# Wilssen_core_v0_204a.net
KiCad netlist of a schematic drawn in EAGLE
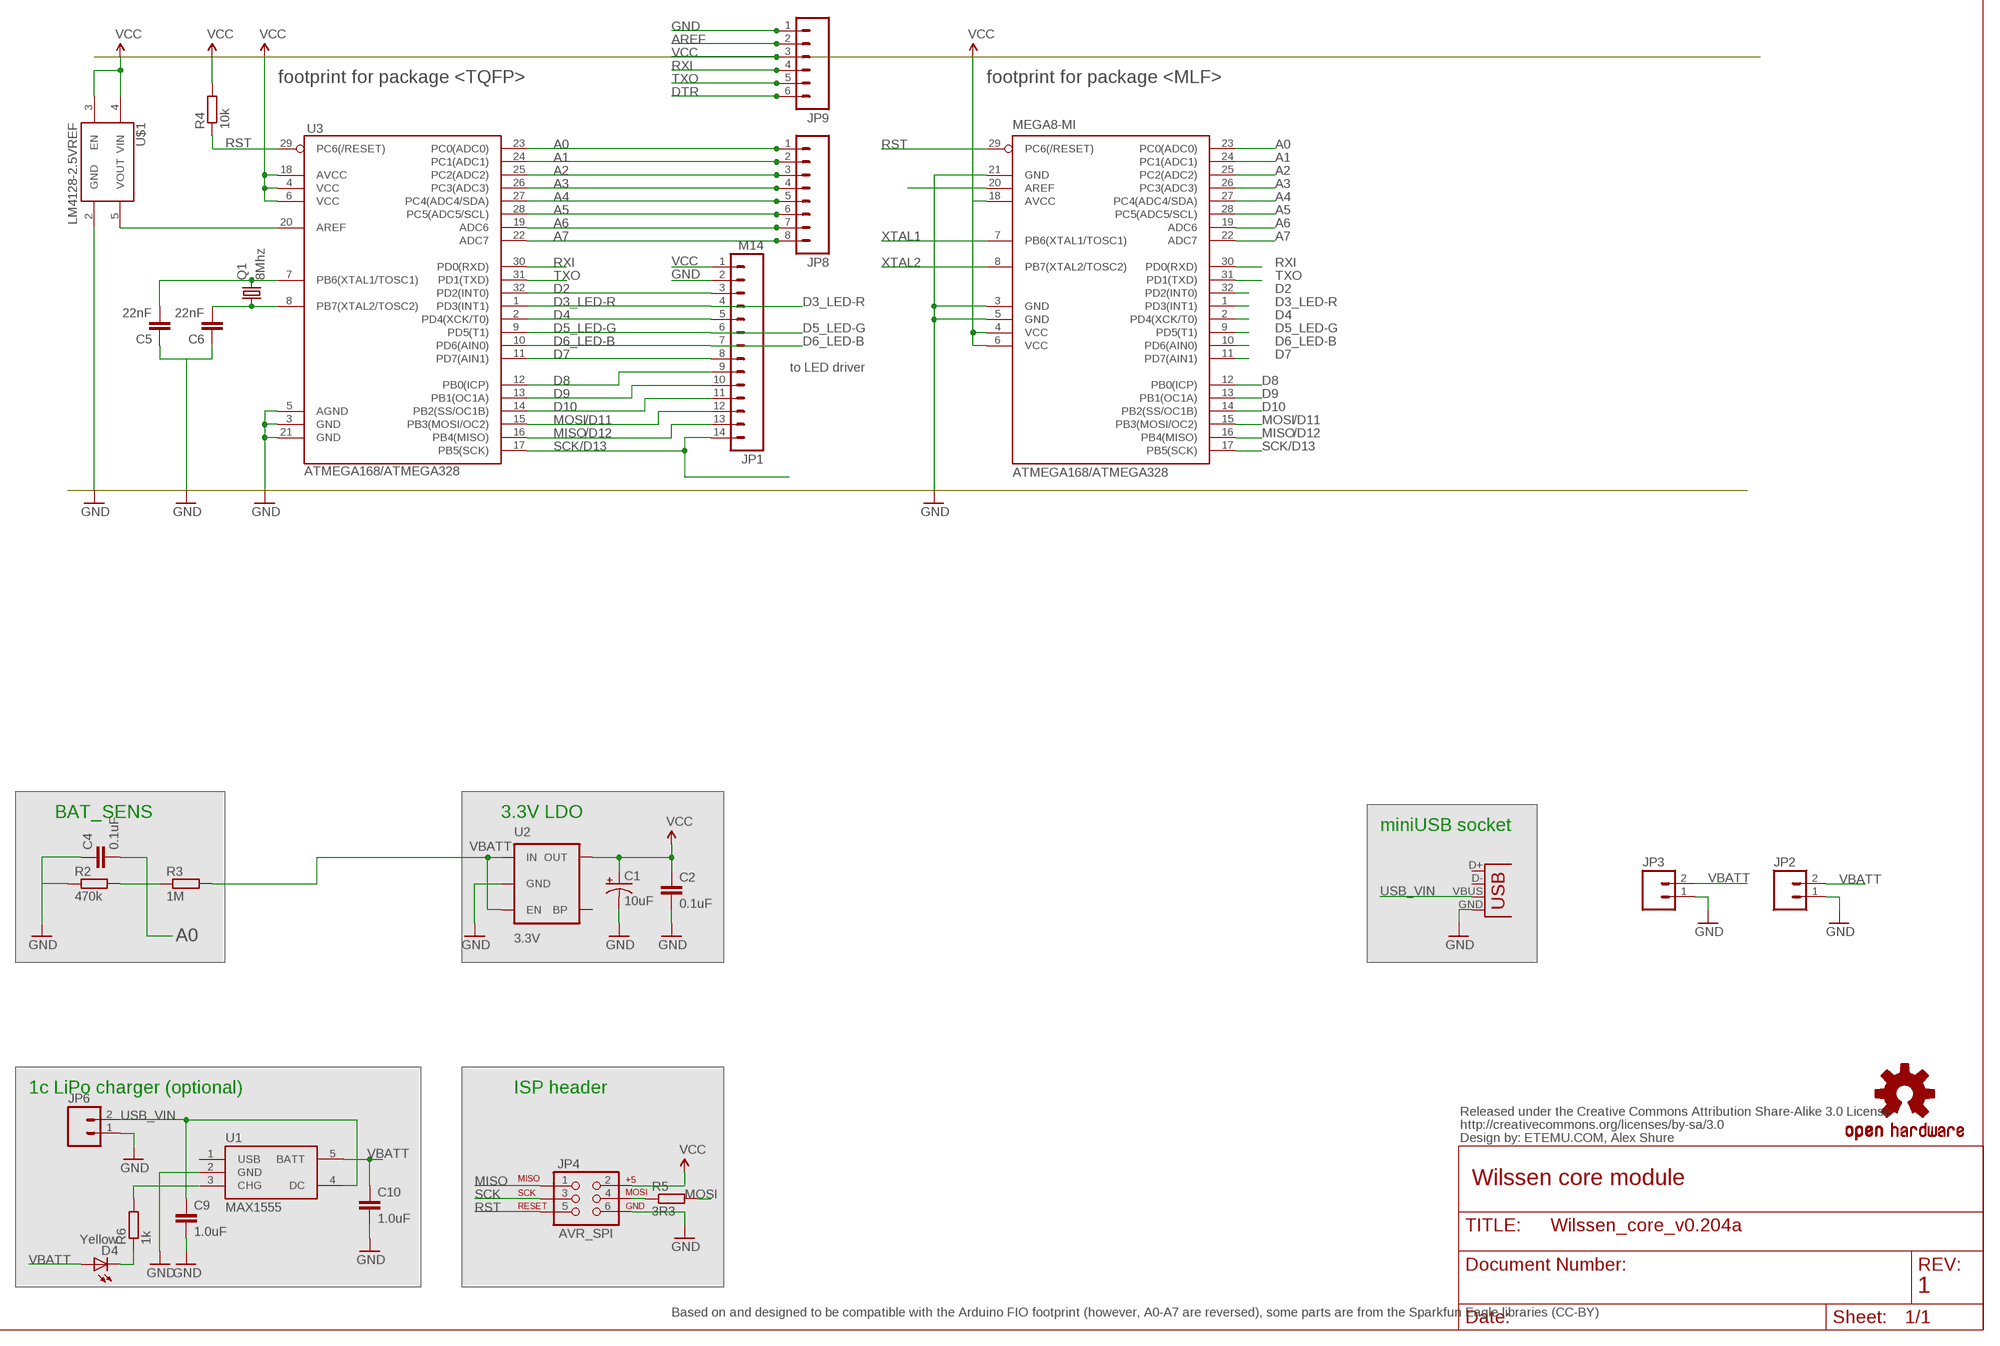
[diagram p0: schematic, sheet 1, part 1 of 2]
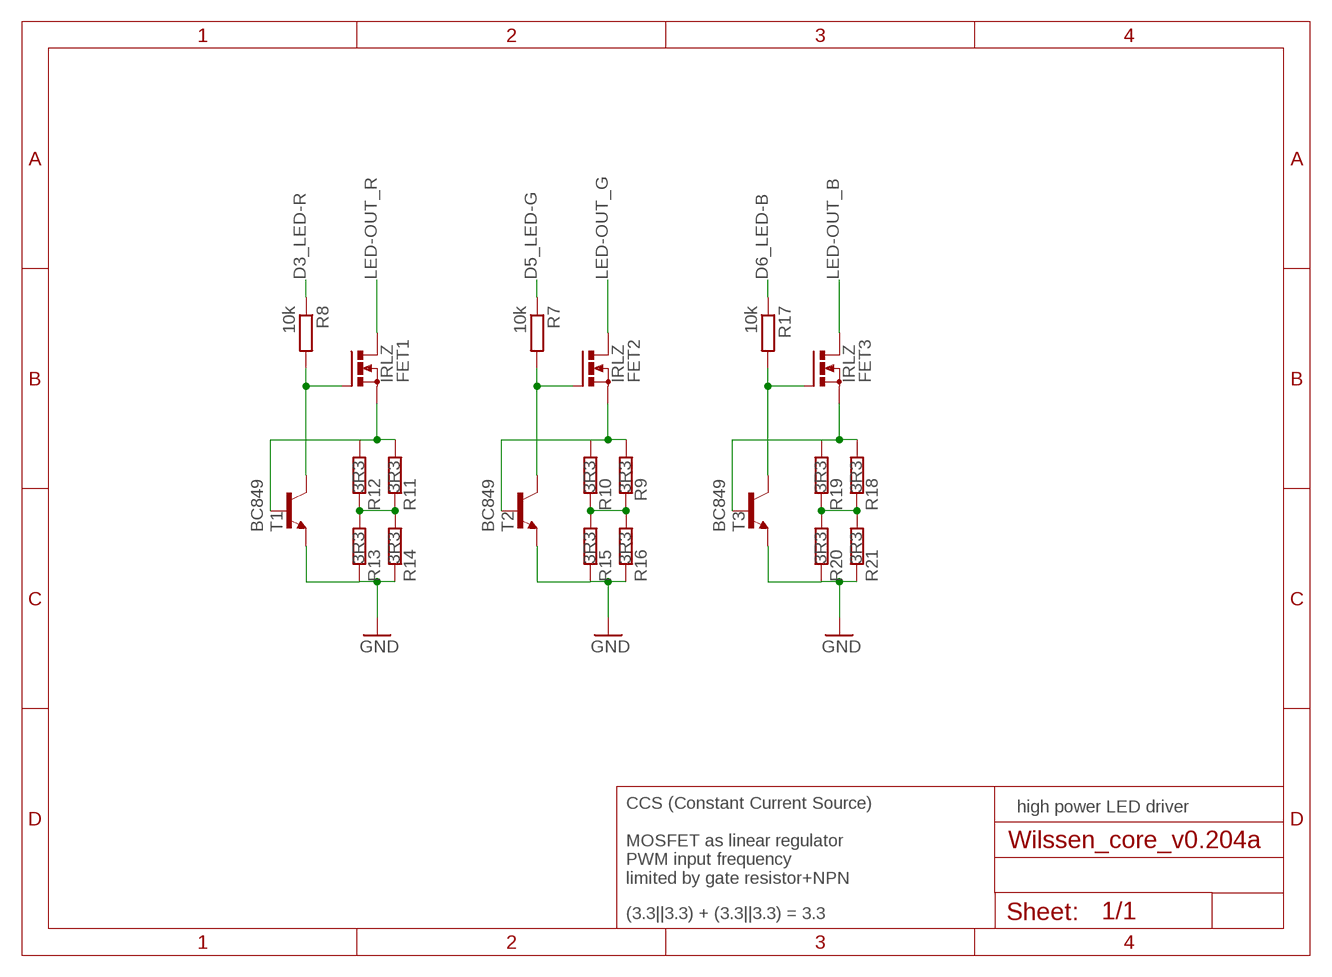
[diagram p1: schematic, sheet 1, part 2 of 2]

(export (version "E")
  (design (tool "Eeschema 10.0.6"))
  (components
    (comp (ref "ATMEGA168/ATMEGA328")
      (value "MEGA8-MI")
      (footprint "eagle-import:MLF32")
      (fields (field (name "MPN") "ATMEGA88PA-MU"))
      (libsource (lib "eagle-import") (part "MEGA8-MI"))
    )
    (comp (ref "C1")
      (value "10uF")
      (footprint "eagle-import:EIA3216")
      (libsource (lib "eagle-import") (part "CAP_POL1206"))
    )
    (comp (ref "C2")
      (value "0.1uF")
      (footprint "eagle-import:0805")
      (libsource (lib "eagle-import") (part "CAP0805"))
    )
    (comp (ref "C4")
      (value "0.1uF")
      (footprint "eagle-import:0805")
      (libsource (lib "eagle-import") (part "CAP0805"))
    )
    (comp (ref "C5")
      (value "22nF")
      (footprint "eagle-import:0805")
      (libsource (lib "eagle-import") (part "CAP0805"))
    )
    (comp (ref "C6")
      (value "22nF")
      (footprint "eagle-import:0805")
      (libsource (lib "eagle-import") (part "CAP0805"))
    )
    (comp (ref "C9")
      (value "1.0uF")
      (footprint "eagle-import:0805")
      (libsource (lib "eagle-import") (part "CAP0805"))
    )
    (comp (ref "C10")
      (value "1.0uF")
      (footprint "eagle-import:0805")
      (libsource (lib "eagle-import") (part "CAP0805"))
    )
    (comp (ref "CC_TEXT1")
      (value "CREATIVE_COMMONS")
      (footprint "eagle-import:CREATIVE_COMMONS")
      (libsource (lib "eagle-import") (part "CREATIVE_COMMONS"))
    )
    (comp (ref "D4")
      (value "Yellow")
      (footprint "eagle-import:LED-0603")
      (libsource (lib "eagle-import") (part "LED0603"))
    )
    (comp (ref "FET1")
      (value "IRLZ")
      (footprint "eagle-import:TO220BV")
      (libsource (lib "eagle-import") (part "PMOSFET_NTO220BV"))
    )
    (comp (ref "FET2")
      (value "IRLZ")
      (footprint "eagle-import:TO220BV")
      (libsource (lib "eagle-import") (part "PMOSFET_NTO220BV"))
    )
    (comp (ref "FET3")
      (value "IRLZ")
      (footprint "eagle-import:TO220BV")
      (libsource (lib "eagle-import") (part "PMOSFET_NTO220BV"))
    )
    (comp (ref "JP1")
      (value "M14")
      (footprint "eagle-import:1X14")
      (libsource (lib "eagle-import") (part "M14"))
    )
    (comp (ref "JP2")
      (value "M02PTH")
      (footprint "eagle-import:1X02")
      (libsource (lib "eagle-import") (part "M02PTH"))
    )
    (comp (ref "JP3")
      (value "M02-JST-2MM-SMT")
      (footprint "eagle-import:S2B-PH")
      (libsource (lib "eagle-import") (part "M02-JST-2MM-SMT"))
    )
    (comp (ref "JP4")
      (value "AVR_SPI")
      (footprint "eagle-import:2X3")
      (libsource (lib "eagle-import") (part "AVR_SPI_PRG_6PTH"))
    )
    (comp (ref "JP6")
      (value "M02PTH")
      (footprint "eagle-import:1X02")
      (libsource (lib "eagle-import") (part "M02PTH"))
    )
    (comp (ref "JP8")
      (value "M081X08")
      (footprint "eagle-import:1X08")
      (libsource (lib "eagle-import") (part "M081X08"))
    )
    (comp (ref "JP9")
      (value "M06SIP")
      (footprint "eagle-import:1X06")
      (libsource (lib "eagle-import") (part "M06SIP"))
    )
    (comp (ref "LOGO1")
      (value "OSHW-LOGOS")
      (footprint "eagle-import:OSHW-LOGO-S")
      (libsource (lib "eagle-import") (part "OSHW-LOGOS"))
    )
    (comp (ref "Q1")
      (value "8Mhz")
      (footprint "eagle-import:SM49")
      (libsource (lib "eagle-import") (part "CRYSTALSM49"))
    )
    (comp (ref "R2")
      (value "470k")
      (footprint "eagle-import:R0805")
      (libsource (lib "eagle-import") (part "R-EU_R0805"))
    )
    (comp (ref "R3")
      (value "1M")
      (footprint "eagle-import:R0805")
      (libsource (lib "eagle-import") (part "R-EU_R0805"))
    )
    (comp (ref "R4")
      (value "10k")
      (footprint "eagle-import:R0805")
      (libsource (lib "eagle-import") (part "R-EU_R0805"))
    )
    (comp (ref "R5")
      (value "3R3")
      (footprint "eagle-import:R1206")
      (libsource (lib "eagle-import") (part "R-EU_R1206"))
    )
    (comp (ref "R6")
      (value "1k")
      (footprint "eagle-import:R0805")
      (libsource (lib "eagle-import") (part "R-EU_R0805"))
    )
    (comp (ref "R7")
      (value "10k")
      (footprint "eagle-import:R0805")
      (libsource (lib "eagle-import") (part "resistor_R-EU_R0805"))
    )
    (comp (ref "R8")
      (value "10k")
      (footprint "eagle-import:R0805")
      (libsource (lib "eagle-import") (part "resistor_R-EU_R0805"))
    )
    (comp (ref "R9")
      (value "3R3")
      (footprint "eagle-import:R1206")
      (libsource (lib "eagle-import") (part "resistor_R-EU_R1206"))
    )
    (comp (ref "R10")
      (value "3R3")
      (footprint "eagle-import:R1206")
      (libsource (lib "eagle-import") (part "resistor_R-EU_R1206"))
    )
    (comp (ref "R11")
      (value "3R3")
      (footprint "eagle-import:R1206")
      (libsource (lib "eagle-import") (part "resistor_R-EU_R1206"))
    )
    (comp (ref "R12")
      (value "3R3")
      (footprint "eagle-import:R1206")
      (libsource (lib "eagle-import") (part "resistor_R-EU_R1206"))
    )
    (comp (ref "R13")
      (value "3R3")
      (footprint "eagle-import:R1206")
      (libsource (lib "eagle-import") (part "resistor_R-EU_R1206"))
    )
    (comp (ref "R14")
      (value "3R3")
      (footprint "eagle-import:R1206")
      (libsource (lib "eagle-import") (part "resistor_R-EU_R1206"))
    )
    (comp (ref "R15")
      (value "3R3")
      (footprint "eagle-import:R1206")
      (libsource (lib "eagle-import") (part "resistor_R-EU_R1206"))
    )
    (comp (ref "R16")
      (value "3R3")
      (footprint "eagle-import:R1206")
      (libsource (lib "eagle-import") (part "resistor_R-EU_R1206"))
    )
    (comp (ref "R17")
      (value "10k")
      (footprint "eagle-import:R0805")
      (libsource (lib "eagle-import") (part "resistor_R-EU_R0805"))
    )
    (comp (ref "R18")
      (value "3R3")
      (footprint "eagle-import:R1206")
      (libsource (lib "eagle-import") (part "resistor_R-EU_R1206"))
    )
    (comp (ref "R19")
      (value "3R3")
      (footprint "eagle-import:R1206")
      (libsource (lib "eagle-import") (part "resistor_R-EU_R1206"))
    )
    (comp (ref "R20")
      (value "3R3")
      (footprint "eagle-import:R1206")
      (libsource (lib "eagle-import") (part "resistor_R-EU_R1206"))
    )
    (comp (ref "R21")
      (value "3R3")
      (footprint "eagle-import:R1206")
      (libsource (lib "eagle-import") (part "resistor_R-EU_R1206"))
    )
    (comp (ref "T1")
      (value "BC849")
      (footprint "eagle-import:SOT23")
      (libsource (lib "eagle-import") (part "BC849"))
    )
    (comp (ref "T2")
      (value "BC849")
      (footprint "eagle-import:SOT23")
      (libsource (lib "eagle-import") (part "BC849"))
    )
    (comp (ref "T3")
      (value "BC849")
      (footprint "eagle-import:SOT23")
      (libsource (lib "eagle-import") (part "BC849"))
    )
    (comp (ref "U$1")
      (value "LM4128-2.5VREF")
      (footprint "eagle-import:SOT23-5")
      (libsource (lib "eagle-import") (part "LM4128-2.5VREF"))
    )
    (comp (ref "U1")
      (value "MAX1555")
      (footprint "eagle-import:SOT23-5")
      (libsource (lib "eagle-import") (part "MAX1555"))
    )
    (comp (ref "U2")
      (value "3.3V")
      (footprint "eagle-import:SOT23-5")
      (libsource (lib "eagle-import") (part "V_REG_LDOSMD"))
    )
    (comp (ref "U3")
      (value "ATMEGA168/ATMEGA328")
      (footprint "eagle-import:TQFP32-08")
      (libsource (lib "eagle-import") (part "ATMEGA168"))
    )
    (comp (ref "X1")
      (value "USBSMD")
      (footprint "eagle-import:USB-MINIB")
      (libsource (lib "eagle-import") (part "USBSMD"))
    )
  )
  (nets
    (net (code "1") (name "/A0") (class "Default")
      (node (ref "ATMEGA168/ATMEGA328") (pin "23") (pinfunction "PC0(ADC0)_23") (pintype "bidirectional"))
      (node (ref "C4") (pin "2") (pinfunction "2_2") (pintype "passive"))
      (node (ref "JP8") (pin "1") (pinfunction "1_1") (pintype "passive"))
      (node (ref "R2") (pin "2") (pinfunction "2_2") (pintype "passive"))
      (node (ref "R3") (pin "1") (pinfunction "1_1") (pintype "passive"))
      (node (ref "U3") (pin "23") (pinfunction "PC0(ADC0)_23") (pintype "bidirectional"))
    )
    (net (code "2") (name "/A1") (class "Default")
      (node (ref "ATMEGA168/ATMEGA328") (pin "24") (pinfunction "PC1(ADC1)_24") (pintype "bidirectional"))
      (node (ref "JP8") (pin "2") (pinfunction "2_2") (pintype "passive"))
      (node (ref "U3") (pin "24") (pinfunction "PC1(ADC1)_24") (pintype "bidirectional"))
    )
    (net (code "3") (name "/A2") (class "Default")
      (node (ref "ATMEGA168/ATMEGA328") (pin "25") (pinfunction "PC2(ADC2)_25") (pintype "bidirectional"))
      (node (ref "JP8") (pin "3") (pinfunction "3_3") (pintype "passive"))
      (node (ref "U3") (pin "25") (pinfunction "PC2(ADC2)_25") (pintype "bidirectional"))
    )
    (net (code "4") (name "/A3") (class "Default")
      (node (ref "ATMEGA168/ATMEGA328") (pin "26") (pinfunction "PC3(ADC3)_26") (pintype "bidirectional"))
      (node (ref "JP8") (pin "4") (pinfunction "4_4") (pintype "passive"))
      (node (ref "U3") (pin "26") (pinfunction "PC3(ADC3)_26") (pintype "bidirectional"))
    )
    (net (code "5") (name "/A4") (class "Default")
      (node (ref "ATMEGA168/ATMEGA328") (pin "27") (pinfunction "PC4(ADC4/SDA)_27") (pintype "bidirectional"))
      (node (ref "JP8") (pin "5") (pinfunction "5_5") (pintype "passive"))
      (node (ref "U3") (pin "27") (pinfunction "PC4(ADC4/SDA)_27") (pintype "bidirectional"))
    )
    (net (code "6") (name "/A5") (class "Default")
      (node (ref "ATMEGA168/ATMEGA328") (pin "28") (pinfunction "PC5(ADC5/SCL)_28") (pintype "bidirectional"))
      (node (ref "JP8") (pin "6") (pinfunction "6_6") (pintype "passive"))
      (node (ref "U3") (pin "28") (pinfunction "PC5(ADC5/SCL)_28") (pintype "bidirectional"))
    )
    (net (code "7") (name "/A6") (class "Default")
      (node (ref "ATMEGA168/ATMEGA328") (pin "19") (pinfunction "ADC6_19") (pintype "bidirectional"))
      (node (ref "JP8") (pin "7") (pinfunction "7_7") (pintype "passive"))
      (node (ref "U3") (pin "19") (pinfunction "ADC6_19") (pintype "bidirectional"))
    )
    (net (code "8") (name "/A7") (class "Default")
      (node (ref "ATMEGA168/ATMEGA328") (pin "22") (pinfunction "ADC7_22") (pintype "bidirectional"))
      (node (ref "JP8") (pin "8") (pinfunction "8_8") (pintype "passive"))
      (node (ref "U3") (pin "22") (pinfunction "ADC7_22") (pintype "bidirectional"))
    )
    (net (code "9") (name "/AREF") (class "Default")
      (node (ref "ATMEGA168/ATMEGA328") (pin "20") (pinfunction "AREF_20") (pintype "passive"))
      (node (ref "JP9") (pin "2") (pinfunction "2_2") (pintype "passive"))
      (node (ref "U$1") (pin "5") (pinfunction "VOUT_5") (pintype "bidirectional"))
      (node (ref "U3") (pin "20") (pinfunction "AREF_20") (pintype "bidirectional"))
    )
    (net (code "10") (name "/D2") (class "Default")
      (node (ref "ATMEGA168/ATMEGA328") (pin "32") (pinfunction "PD2(INT0)_32") (pintype "bidirectional"))
      (node (ref "JP1") (pin "3") (pinfunction "3_3") (pintype "passive"))
      (node (ref "U3") (pin "32") (pinfunction "PD2(INT0)_32") (pintype "bidirectional"))
    )
    (net (code "11") (name "/D3_LED-R") (class "Default")
      (node (ref "ATMEGA168/ATMEGA328") (pin "1") (pinfunction "PD3(INT1)_1") (pintype "bidirectional"))
      (node (ref "JP1") (pin "4") (pinfunction "4_4") (pintype "passive"))
      (node (ref "R8") (pin "1") (pinfunction "1_1") (pintype "passive"))
      (node (ref "U3") (pin "1") (pinfunction "PD3(INT1)_1") (pintype "bidirectional"))
    )
    (net (code "12") (name "/D4") (class "Default")
      (node (ref "ATMEGA168/ATMEGA328") (pin "2") (pinfunction "PD4(XCK/T0)_2") (pintype "bidirectional"))
      (node (ref "JP1") (pin "5") (pinfunction "5_5") (pintype "passive"))
      (node (ref "U3") (pin "2") (pinfunction "PD4(XCK/T0)_2") (pintype "bidirectional"))
    )
    (net (code "13") (name "/D5_LED-G") (class "Default")
      (node (ref "ATMEGA168/ATMEGA328") (pin "9") (pinfunction "PD5(T1)_9") (pintype "bidirectional"))
      (node (ref "JP1") (pin "6") (pinfunction "6_6") (pintype "passive"))
      (node (ref "R7") (pin "1") (pinfunction "1_1") (pintype "passive"))
      (node (ref "U3") (pin "9") (pinfunction "PD5(T1)_9") (pintype "bidirectional"))
    )
    (net (code "14") (name "/D6_LED-B") (class "Default")
      (node (ref "ATMEGA168/ATMEGA328") (pin "10") (pinfunction "PD6(AIN0)_10") (pintype "bidirectional"))
      (node (ref "JP1") (pin "7") (pinfunction "7_7") (pintype "passive"))
      (node (ref "R17") (pin "1") (pinfunction "1_1") (pintype "passive"))
      (node (ref "U3") (pin "10") (pinfunction "PD6(AIN0)_10") (pintype "bidirectional"))
    )
    (net (code "15") (name "/D7") (class "Default")
      (node (ref "ATMEGA168/ATMEGA328") (pin "11") (pinfunction "PD7(AIN1)_11") (pintype "bidirectional"))
      (node (ref "JP1") (pin "8") (pinfunction "8_8") (pintype "passive"))
      (node (ref "U3") (pin "11") (pinfunction "PD7(AIN1)_11") (pintype "bidirectional"))
    )
    (net (code "16") (name "/D8") (class "Default")
      (node (ref "ATMEGA168/ATMEGA328") (pin "12") (pinfunction "PB0(ICP)_12") (pintype "bidirectional"))
      (node (ref "JP1") (pin "9") (pinfunction "9_9") (pintype "passive"))
      (node (ref "U3") (pin "12") (pinfunction "PB0(ICP)_12") (pintype "bidirectional"))
    )
    (net (code "17") (name "/D9") (class "Default")
      (node (ref "ATMEGA168/ATMEGA328") (pin "13") (pinfunction "PB1(OC1A)_13") (pintype "bidirectional"))
      (node (ref "JP1") (pin "10") (pinfunction "10_10") (pintype "passive"))
      (node (ref "U3") (pin "13") (pinfunction "PB1(OC1A)_13") (pintype "bidirectional"))
    )
    (net (code "18") (name "/D10") (class "Default")
      (node (ref "ATMEGA168/ATMEGA328") (pin "14") (pinfunction "PB2(SS/OC1B)_14") (pintype "bidirectional"))
      (node (ref "JP1") (pin "11") (pinfunction "11_11") (pintype "passive"))
      (node (ref "U3") (pin "14") (pinfunction "PB2(SS/OC1B)_14") (pintype "bidirectional"))
    )
    (net (code "19") (name "/DTR") (class "Default")
      (node (ref "JP9") (pin "6") (pinfunction "6_6") (pintype "passive"))
    )
    (net (code "20") (name "/LED-OUT_B") (class "Default")
      (node (ref "FET3") (pin "D") (pinfunction "D_D") (pintype "passive"))
    )
    (net (code "21") (name "/LED-OUT_G") (class "Default")
      (node (ref "FET2") (pin "D") (pinfunction "D_D") (pintype "passive"))
    )
    (net (code "22") (name "/LED-OUT_R") (class "Default")
      (node (ref "FET1") (pin "D") (pinfunction "D_D") (pintype "passive"))
    )
    (net (code "23") (name "/MISO") (class "Default")
      (node (ref "ATMEGA168/ATMEGA328") (pin "16") (pinfunction "PB4(MISO)_16") (pintype "bidirectional"))
      (node (ref "JP1") (pin "13") (pinfunction "13_13") (pintype "passive"))
      (node (ref "JP4") (pin "1") (pinfunction "1_1") (pintype "passive"))
      (node (ref "U3") (pin "16") (pinfunction "PB4(MISO)_16") (pintype "bidirectional"))
    )
    (net (code "24") (name "/MOSI") (class "Default")
      (node (ref "ATMEGA168/ATMEGA328") (pin "15") (pinfunction "PB3(MOSI/OC2)_15") (pintype "bidirectional"))
      (node (ref "JP1") (pin "12") (pinfunction "12_12") (pintype "passive"))
      (node (ref "R5") (pin "2") (pinfunction "2_2") (pintype "passive"))
      (node (ref "U3") (pin "15") (pinfunction "PB3(MOSI/OC2)_15") (pintype "bidirectional"))
    )
    (net (code "25") (name "/RST") (class "Default")
      (node (ref "ATMEGA168/ATMEGA328") (pin "29") (pinfunction "PC6(/RESET)_29") (pintype "bidirectional"))
      (node (ref "JP4") (pin "5") (pinfunction "5_5") (pintype "passive"))
      (node (ref "R4") (pin "1") (pinfunction "1_1") (pintype "passive"))
      (node (ref "U3") (pin "29") (pinfunction "PC6(/RESET)_29") (pintype "bidirectional"))
    )
    (net (code "26") (name "/RXI") (class "Default")
      (node (ref "ATMEGA168/ATMEGA328") (pin "30") (pinfunction "PD0(RXD)_30") (pintype "bidirectional"))
      (node (ref "JP9") (pin "4") (pinfunction "4_4") (pintype "passive"))
      (node (ref "U3") (pin "30") (pinfunction "PD0(RXD)_30") (pintype "bidirectional"))
    )
    (net (code "27") (name "/SCK") (class "Default")
      (node (ref "ATMEGA168/ATMEGA328") (pin "17") (pinfunction "PB5(SCK)_17") (pintype "bidirectional"))
      (node (ref "JP1") (pin "14") (pinfunction "14_14") (pintype "passive"))
      (node (ref "JP4") (pin "3") (pinfunction "3_3") (pintype "passive"))
      (node (ref "U3") (pin "17") (pinfunction "PB5(SCK)_17") (pintype "bidirectional"))
    )
    (net (code "28") (name "/TXO") (class "Default")
      (node (ref "ATMEGA168/ATMEGA328") (pin "31") (pinfunction "PD1(TXD)_31") (pintype "bidirectional"))
      (node (ref "JP9") (pin "5") (pinfunction "5_5") (pintype "passive"))
      (node (ref "U3") (pin "31") (pinfunction "PD1(TXD)_31") (pintype "bidirectional"))
    )
    (net (code "29") (name "/USB_VIN") (class "Default")
      (node (ref "C9") (pin "1") (pinfunction "1_1") (pintype "passive"))
      (node (ref "JP6") (pin "2") (pinfunction "2_2") (pintype "passive"))
      (node (ref "U1") (pin "4") (pinfunction "DC_4") (pintype "bidirectional"))
      (node (ref "X1") (pin "VBUS") (pinfunction "VBUS_VBUS") (pintype "bidirectional"))
    )
    (net (code "30") (name "/VBATT") (class "Default")
      (node (ref "C10") (pin "1") (pinfunction "1_1") (pintype "passive"))
      (node (ref "D4") (pin "A") (pinfunction "A_A") (pintype "passive"))
      (node (ref "JP2") (pin "2") (pinfunction "2_2") (pintype "passive"))
      (node (ref "JP3") (pin "2") (pinfunction "2_2") (pintype "passive"))
      (node (ref "R3") (pin "2") (pinfunction "2_2") (pintype "passive"))
      (node (ref "U1") (pin "5") (pinfunction "BATT_5") (pintype "bidirectional"))
      (node (ref "U2") (pin "1") (pinfunction "IN_1") (pintype "input"))
      (node (ref "U2") (pin "3") (pinfunction "EN_3") (pintype "input"))
    )
    (net (code "31") (name "/XTAL1") (class "Default")
      (node (ref "ATMEGA168/ATMEGA328") (pin "7") (pinfunction "PB6(XTAL1/TOSC1)_7") (pintype "bidirectional"))
      (node (ref "C5") (pin "2") (pinfunction "2_2") (pintype "passive"))
      (node (ref "Q1") (pin "2") (pinfunction "2_2") (pintype "passive"))
      (node (ref "U3") (pin "7") (pinfunction "PB6(XTAL1/TOSC1)_7") (pintype "bidirectional"))
    )
    (net (code "32") (name "/XTAL2") (class "Default")
      (node (ref "ATMEGA168/ATMEGA328") (pin "8") (pinfunction "PB7(XTAL2/TOSC2)_8") (pintype "bidirectional"))
      (node (ref "C6") (pin "2") (pinfunction "2_2") (pintype "passive"))
      (node (ref "Q1") (pin "1") (pinfunction "1_1") (pintype "passive"))
      (node (ref "U3") (pin "8") (pinfunction "PB7(XTAL2/TOSC2)_8") (pintype "bidirectional"))
    )
    (net (code "33") (name "GND") (class "Default")
      (node (ref "ATMEGA168/ATMEGA328") (pin "21") (pinfunction "GND_21") (pintype "power_in"))
      (node (ref "ATMEGA168/ATMEGA328") (pin "3") (pinfunction "GND_3") (pintype "power_in"))
      (node (ref "ATMEGA168/ATMEGA328") (pin "5") (pinfunction "GND_5") (pintype "power_in"))
      (node (ref "C1") (pin "C") (pinfunction "-_C") (pintype "passive"))
      (node (ref "C10") (pin "2") (pinfunction "2_2") (pintype "passive"))
      (node (ref "C2") (pin "2") (pinfunction "2_2") (pintype "passive"))
      (node (ref "C4") (pin "1") (pinfunction "1_1") (pintype "passive"))
      (node (ref "C5") (pin "1") (pinfunction "1_1") (pintype "passive"))
      (node (ref "C6") (pin "1") (pinfunction "1_1") (pintype "passive"))
      (node (ref "C9") (pin "2") (pinfunction "2_2") (pintype "passive"))
      (node (ref "JP1") (pin "2") (pinfunction "2_2") (pintype "passive"))
      (node (ref "JP2") (pin "1") (pinfunction "1_1") (pintype "passive"))
      (node (ref "JP3") (pin "1") (pinfunction "1_1") (pintype "passive"))
      (node (ref "JP4") (pin "6") (pinfunction "6_6") (pintype "passive"))
      (node (ref "JP6") (pin "1") (pinfunction "1_1") (pintype "passive"))
      (node (ref "JP9") (pin "1") (pinfunction "1_1") (pintype "passive"))
      (node (ref "R13") (pin "2") (pinfunction "2_2") (pintype "passive"))
      (node (ref "R14") (pin "2") (pinfunction "2_2") (pintype "passive"))
      (node (ref "R15") (pin "2") (pinfunction "2_2") (pintype "passive"))
      (node (ref "R16") (pin "2") (pinfunction "2_2") (pintype "passive"))
      (node (ref "R2") (pin "1") (pinfunction "1_1") (pintype "passive"))
      (node (ref "R20") (pin "2") (pinfunction "2_2") (pintype "passive"))
      (node (ref "R21") (pin "2") (pinfunction "2_2") (pintype "passive"))
      (node (ref "T1") (pin "2") (pinfunction "E_2") (pintype "passive"))
      (node (ref "T2") (pin "2") (pinfunction "E_2") (pintype "passive"))
      (node (ref "T3") (pin "2") (pinfunction "E_2") (pintype "passive"))
      (node (ref "U$1") (pin "2") (pinfunction "GND_2") (pintype "bidirectional"))
      (node (ref "U1") (pin "2") (pinfunction "GND_2") (pintype "bidirectional"))
      (node (ref "U2") (pin "2") (pinfunction "GND_2") (pintype "input"))
      (node (ref "U3") (pin "21") (pinfunction "GND_21") (pintype "bidirectional"))
      (node (ref "U3") (pin "3") (pinfunction "GND_3") (pintype "bidirectional"))
      (node (ref "U3") (pin "5") (pinfunction "AGND_5") (pintype "bidirectional"))
      (node (ref "X1") (pin "GND") (pinfunction "GND_GND") (pintype "bidirectional"))
    )
    (net (code "34") (name "Net-(D4-PadC)") (class "Default")
      (node (ref "D4") (pin "C") (pinfunction "C_C") (pintype "passive"))
      (node (ref "R6") (pin "1") (pinfunction "1_1") (pintype "passive"))
    )
    (net (code "35") (name "Net-(JP4-Pad4)") (class "Default")
      (node (ref "JP4") (pin "4") (pinfunction "4_4") (pintype "passive"))
      (node (ref "R5") (pin "1") (pinfunction "1_1") (pintype "passive"))
    )
    (net (code "36") (name "Net-(R10-Pad2)") (class "Default")
      (node (ref "R10") (pin "2") (pinfunction "2_2") (pintype "passive"))
      (node (ref "R15") (pin "1") (pinfunction "1_1") (pintype "passive"))
      (node (ref "R16") (pin "1") (pinfunction "1_1") (pintype "passive"))
      (node (ref "R9") (pin "2") (pinfunction "2_2") (pintype "passive"))
    )
    (net (code "37") (name "Net-(R11-Pad2)") (class "Default")
      (node (ref "R11") (pin "2") (pinfunction "2_2") (pintype "passive"))
      (node (ref "R12") (pin "2") (pinfunction "2_2") (pintype "passive"))
      (node (ref "R13") (pin "1") (pinfunction "1_1") (pintype "passive"))
      (node (ref "R14") (pin "1") (pinfunction "1_1") (pintype "passive"))
    )
    (net (code "38") (name "Net-(R18-Pad2)") (class "Default")
      (node (ref "R18") (pin "2") (pinfunction "2_2") (pintype "passive"))
      (node (ref "R19") (pin "2") (pinfunction "2_2") (pintype "passive"))
      (node (ref "R20") (pin "1") (pinfunction "1_1") (pintype "passive"))
      (node (ref "R21") (pin "1") (pinfunction "1_1") (pintype "passive"))
    )
    (net (code "39") (name "Net-(T1-B)") (class "Default")
      (node (ref "FET1") (pin "S") (pinfunction "S_S") (pintype "passive"))
      (node (ref "R11") (pin "1") (pinfunction "1_1") (pintype "passive"))
      (node (ref "R12") (pin "1") (pinfunction "1_1") (pintype "passive"))
      (node (ref "T1") (pin "1") (pinfunction "B_1") (pintype "passive"))
    )
    (net (code "40") (name "Net-(T1-C)") (class "Default")
      (node (ref "FET1") (pin "G") (pinfunction "G_G") (pintype "passive"))
      (node (ref "R8") (pin "2") (pinfunction "2_2") (pintype "passive"))
      (node (ref "T1") (pin "3") (pinfunction "C_3") (pintype "passive"))
    )
    (net (code "41") (name "Net-(T2-B)") (class "Default")
      (node (ref "FET2") (pin "S") (pinfunction "S_S") (pintype "passive"))
      (node (ref "R10") (pin "1") (pinfunction "1_1") (pintype "passive"))
      (node (ref "R9") (pin "1") (pinfunction "1_1") (pintype "passive"))
      (node (ref "T2") (pin "1") (pinfunction "B_1") (pintype "passive"))
    )
    (net (code "42") (name "Net-(T2-C)") (class "Default")
      (node (ref "FET2") (pin "G") (pinfunction "G_G") (pintype "passive"))
      (node (ref "R7") (pin "2") (pinfunction "2_2") (pintype "passive"))
      (node (ref "T2") (pin "3") (pinfunction "C_3") (pintype "passive"))
    )
    (net (code "43") (name "Net-(T3-B)") (class "Default")
      (node (ref "FET3") (pin "S") (pinfunction "S_S") (pintype "passive"))
      (node (ref "R18") (pin "1") (pinfunction "1_1") (pintype "passive"))
      (node (ref "R19") (pin "1") (pinfunction "1_1") (pintype "passive"))
      (node (ref "T3") (pin "1") (pinfunction "B_1") (pintype "passive"))
    )
    (net (code "44") (name "Net-(T3-C)") (class "Default")
      (node (ref "FET3") (pin "G") (pinfunction "G_G") (pintype "passive"))
      (node (ref "R17") (pin "2") (pinfunction "2_2") (pintype "passive"))
      (node (ref "T3") (pin "3") (pinfunction "C_3") (pintype "passive"))
    )
    (net (code "45") (name "Net-(U1-CHG)") (class "Default")
      (node (ref "R6") (pin "2") (pinfunction "2_2") (pintype "passive"))
      (node (ref "U1") (pin "3") (pinfunction "CHG_3") (pintype "bidirectional"))
    )
    (net (code "46") (name "VCC") (class "Default")
      (node (ref "ATMEGA168/ATMEGA328") (pin "18") (pinfunction "AVCC_18") (pintype "power_in"))
      (node (ref "ATMEGA168/ATMEGA328") (pin "4") (pinfunction "VCC_4") (pintype "power_in"))
      (node (ref "ATMEGA168/ATMEGA328") (pin "6") (pinfunction "VCC_6") (pintype "power_in"))
      (node (ref "C1") (pin "A") (pinfunction "+_A") (pintype "passive"))
      (node (ref "C2") (pin "1") (pinfunction "1_1") (pintype "passive"))
      (node (ref "JP1") (pin "1") (pinfunction "1_1") (pintype "passive"))
      (node (ref "JP4") (pin "2") (pinfunction "2_2") (pintype "passive"))
      (node (ref "JP9") (pin "3") (pinfunction "3_3") (pintype "passive"))
      (node (ref "R4") (pin "2") (pinfunction "2_2") (pintype "passive"))
      (node (ref "U$1") (pin "3") (pinfunction "EN_3") (pintype "bidirectional"))
      (node (ref "U$1") (pin "4") (pinfunction "VIN_4") (pintype "bidirectional"))
      (node (ref "U2") (pin "5") (pinfunction "OUT_5") (pintype "passive"))
      (node (ref "U3") (pin "18") (pinfunction "AVCC_18") (pintype "bidirectional"))
      (node (ref "U3") (pin "4") (pinfunction "VCC_4") (pintype "bidirectional"))
      (node (ref "U3") (pin "6") (pinfunction "VCC_6") (pintype "bidirectional"))
    )
    (net (code "47") (name "unconnected-(U1-USB-Pad1)") (class "Default")
      (node (ref "U1") (pin "1") (pinfunction "USB_1") (pintype "bidirectional"))
    )
    (net (code "48") (name "unconnected-(U2-BP-Pad4)") (class "Default")
      (node (ref "U2") (pin "4") (pinfunction "BP_4") (pintype "input"))
    )
    (net (code "49") (name "unconnected-(X1-PadD+)") (class "Default")
      (node (ref "X1") (pin "D+") (pinfunction "D+_D+") (pintype "bidirectional"))
    )
    (net (code "50") (name "unconnected-(X1-PadD-)") (class "Default")
      (node (ref "X1") (pin "D-") (pinfunction "D-_D-") (pintype "bidirectional"))
    )
  )
)
